# ADC.net
KiCad netlist of a schematic drawn in Altium Designer
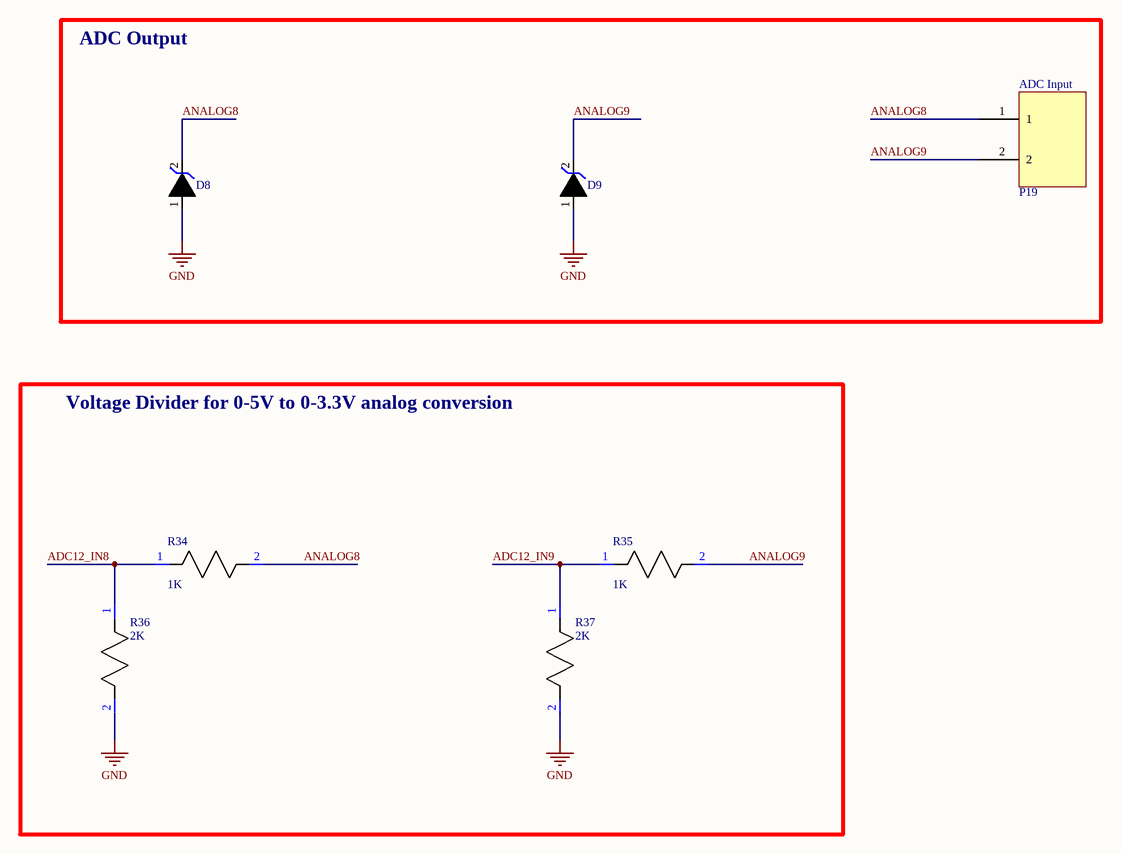
[diagram p0: ADC.SchDoc]

(export (version "E")
  (design (tool "Eeschema 10.0.6"))
  (components
    (comp (ref "D8")
      (value "TVS")
      (footprint "0805 TVS DIODE")
      (description "Schematic for TVS diode")
      (libsource (lib "Lib") (part "TVS Diode"))
    )
    (comp (ref "D9")
      (value "TVS")
      (footprint "0805 TVS DIODE")
      (description "Schematic for TVS diode")
      (libsource (lib "Lib") (part "TVS Diode"))
    )
    (comp (ref "P19")
      (value "ADC Input")
      (footprint "WR-TBL 322 2H")
      (description "322 series 2 pin header")
      (libsource (lib "Lib") (part "322-2H"))
    )
    (comp (ref "R34")
      (value "1K")
      (footprint "0603 RES")
      (description "Can be used for SMD resistors")
      (fields (field (name "Comment") "Resistor"))
      (libsource (lib "Lib") (part "0603 Res"))
    )
    (comp (ref "R35")
      (value "1K")
      (footprint "0603 RES")
      (description "Can be used for SMD resistors")
      (fields (field (name "Comment") "Resistor"))
      (libsource (lib "Lib") (part "0603 Res"))
    )
    (comp (ref "R36")
      (value "2K")
      (footprint "0603 RES")
      (description "Can be used for SMD resistors")
      (fields (field (name "Comment") "Resistor"))
      (libsource (lib "Lib") (part "0603 Res"))
    )
    (comp (ref "R37")
      (value "2K")
      (footprint "0603 RES")
      (description "Can be used for SMD resistors")
      (fields (field (name "Comment") "Resistor"))
      (libsource (lib "Lib") (part "0603 Res"))
    )
  )
  (nets
    (net (code "1") (name "/ADC12_IN8") (class "Default")
      (node (ref "R34") (pin "1") (pinfunction "22_1") (pintype "passive"))
      (node (ref "R36") (pin "1") (pinfunction "22_1") (pintype "passive"))
    )
    (net (code "2") (name "/ADC12_IN9") (class "Default")
      (node (ref "R35") (pin "1") (pinfunction "22_1") (pintype "passive"))
      (node (ref "R37") (pin "1") (pinfunction "22_1") (pintype "passive"))
    )
    (net (code "3") (name "/ANALOG8") (class "Default")
      (node (ref "D8") (pin "2") (pinfunction "2_2") (pintype "passive"))
      (node (ref "P19") (pin "1") (pinfunction "1_1") (pintype "passive"))
      (node (ref "R34") (pin "2") (pinfunction "21_2") (pintype "passive"))
    )
    (net (code "4") (name "/ANALOG9") (class "Default")
      (node (ref "D9") (pin "2") (pinfunction "2_2") (pintype "passive"))
      (node (ref "P19") (pin "2") (pinfunction "2_2") (pintype "passive"))
      (node (ref "R35") (pin "2") (pinfunction "21_2") (pintype "passive"))
    )
    (net (code "5") (name "GND") (class "Default")
      (node (ref "D8") (pin "1") (pinfunction "1_1") (pintype "passive"))
      (node (ref "D9") (pin "1") (pinfunction "1_1") (pintype "passive"))
      (node (ref "R36") (pin "2") (pinfunction "21_2") (pintype "passive"))
      (node (ref "R37") (pin "2") (pinfunction "21_2") (pintype "passive"))
    )
  )
)
